# BMS_AFE_-_Cell_Balancing.net
KiCad netlist of a schematic drawn in Altium Designer
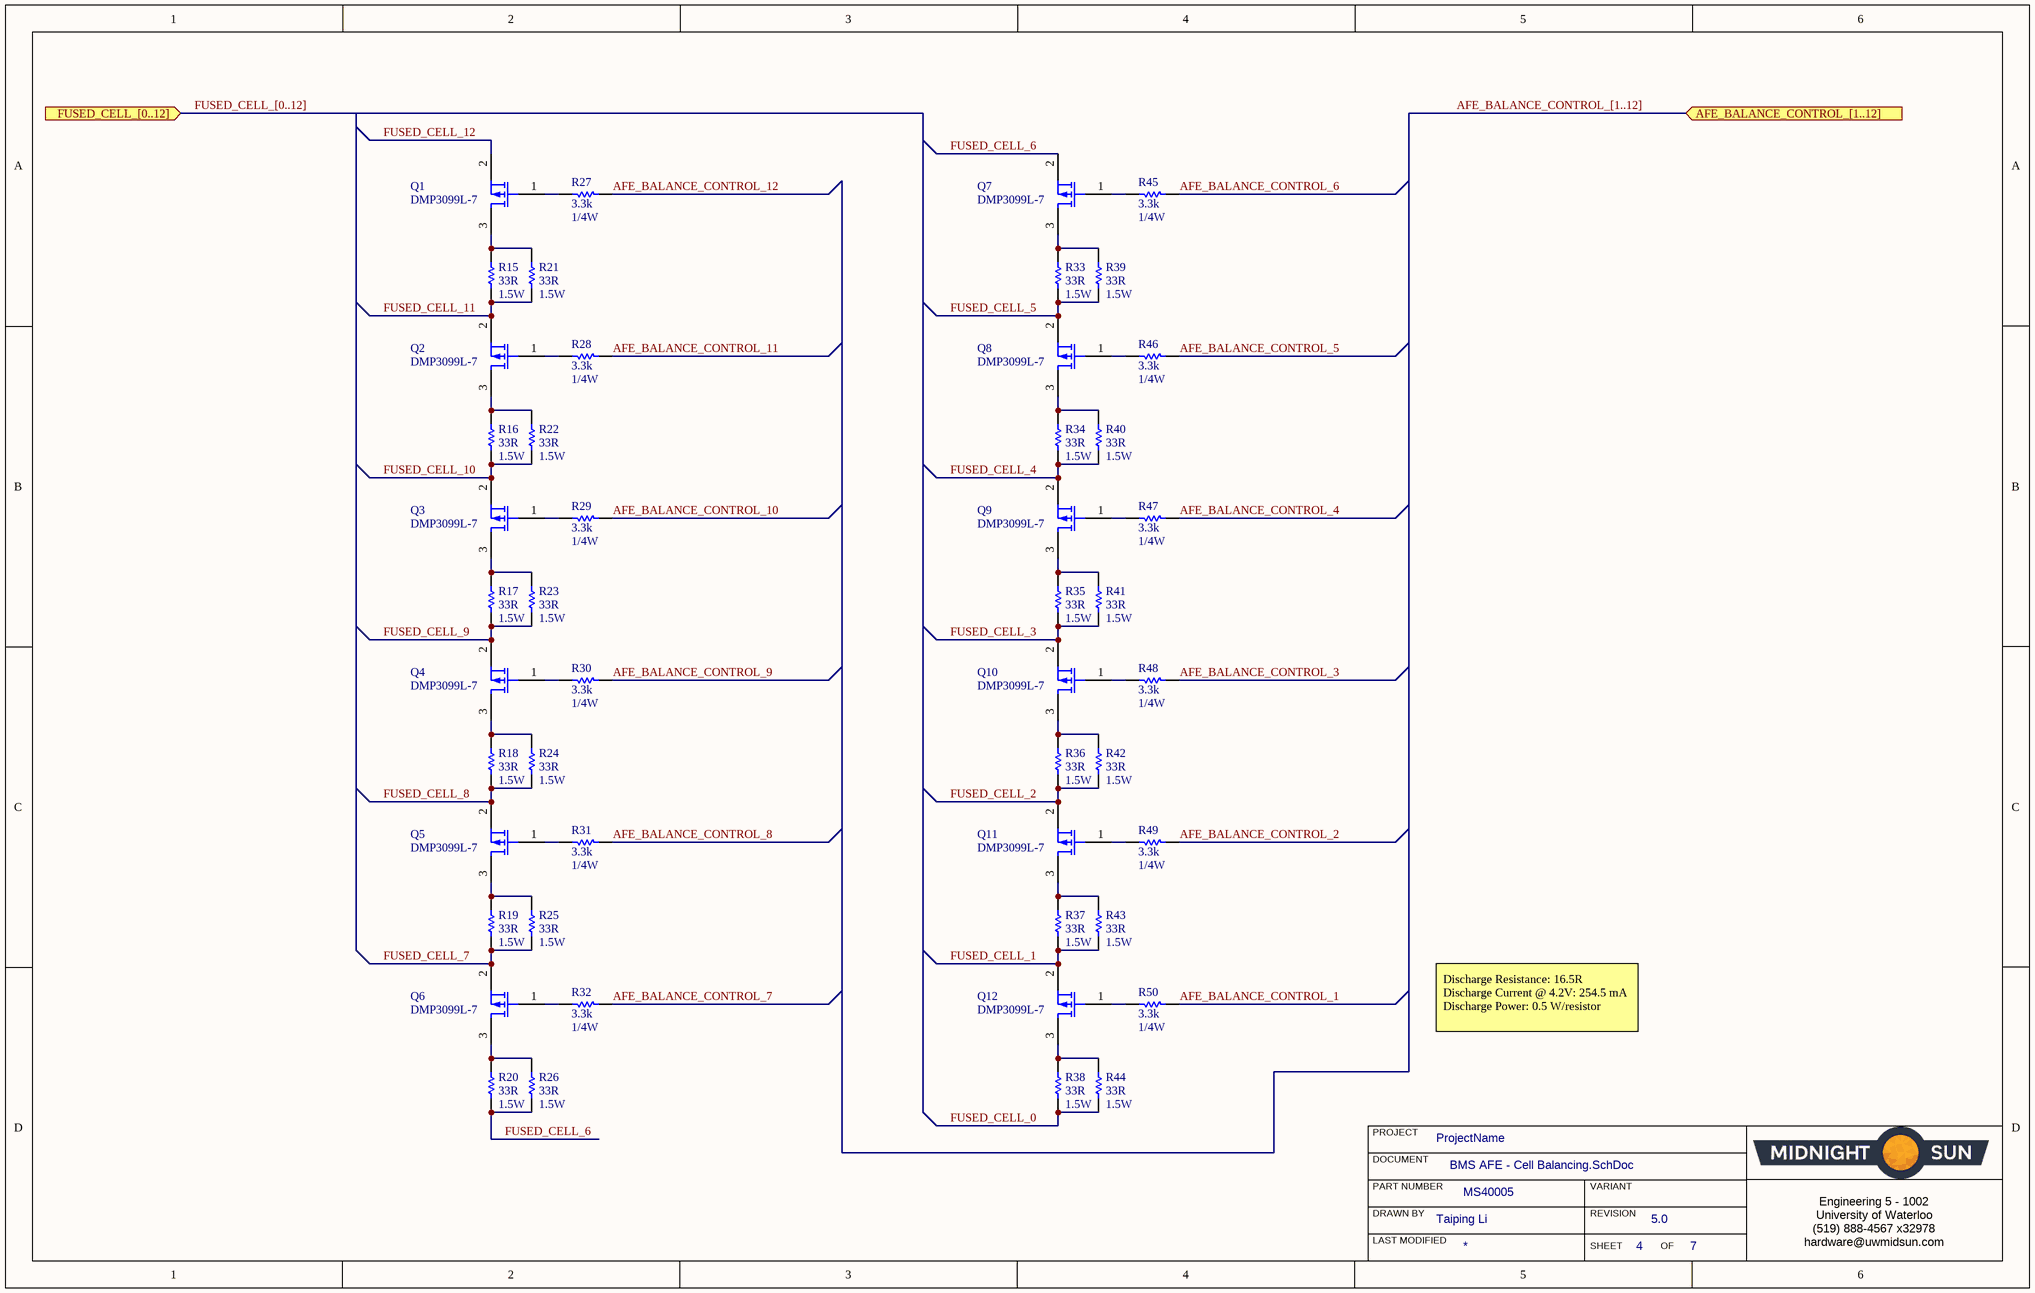
[diagram p0: BMS AFE - Cell Balancing.SchDoc]

(export (version "E")
  (design (tool "Eeschema 10.0.6"))
  (components
    (comp (ref "Q1")
      (value "MOSFET P-CH 30V 3.8A SOT-23")
      (footprint "MOSFET P-CH 30V 3.8A SOT-23")
      (description "P-Channel 30V 3.8A (Ta) 1.08W (Ta) Surface Mount SOT-23")
      (fields
        (field (name "MANUFACTURER") "Diodes Incorporated")
        (field (name "MANUFACTURER PART NUMBER") "DMP3099L-7")
      )
      (libsource (lib "Schematic Diagrams") (part "MOSFET P-CH 30V 3.8A SOT-23"))
    )
    (comp (ref "Q2")
      (value "MOSFET P-CH 30V 3.8A SOT-23")
      (footprint "MOSFET P-CH 30V 3.8A SOT-23")
      (description "P-Channel 30V 3.8A (Ta) 1.08W (Ta) Surface Mount SOT-23")
      (fields
        (field (name "MANUFACTURER") "Diodes Incorporated")
        (field (name "MANUFACTURER PART NUMBER") "DMP3099L-7")
      )
      (libsource (lib "Schematic Diagrams") (part "MOSFET P-CH 30V 3.8A SOT-23"))
    )
    (comp (ref "Q3")
      (value "MOSFET P-CH 30V 3.8A SOT-23")
      (footprint "MOSFET P-CH 30V 3.8A SOT-23")
      (description "P-Channel 30V 3.8A (Ta) 1.08W (Ta) Surface Mount SOT-23")
      (fields
        (field (name "MANUFACTURER") "Diodes Incorporated")
        (field (name "MANUFACTURER PART NUMBER") "DMP3099L-7")
      )
      (libsource (lib "Schematic Diagrams") (part "MOSFET P-CH 30V 3.8A SOT-23"))
    )
    (comp (ref "Q4")
      (value "MOSFET P-CH 30V 3.8A SOT-23")
      (footprint "MOSFET P-CH 30V 3.8A SOT-23")
      (description "P-Channel 30V 3.8A (Ta) 1.08W (Ta) Surface Mount SOT-23")
      (fields
        (field (name "MANUFACTURER") "Diodes Incorporated")
        (field (name "MANUFACTURER PART NUMBER") "DMP3099L-7")
      )
      (libsource (lib "Schematic Diagrams") (part "MOSFET P-CH 30V 3.8A SOT-23"))
    )
    (comp (ref "Q5")
      (value "MOSFET P-CH 30V 3.8A SOT-23")
      (footprint "MOSFET P-CH 30V 3.8A SOT-23")
      (description "P-Channel 30V 3.8A (Ta) 1.08W (Ta) Surface Mount SOT-23")
      (fields
        (field (name "MANUFACTURER") "Diodes Incorporated")
        (field (name "MANUFACTURER PART NUMBER") "DMP3099L-7")
      )
      (libsource (lib "Schematic Diagrams") (part "MOSFET P-CH 30V 3.8A SOT-23"))
    )
    (comp (ref "Q6")
      (value "MOSFET P-CH 30V 3.8A SOT-23")
      (footprint "MOSFET P-CH 30V 3.8A SOT-23")
      (description "P-Channel 30V 3.8A (Ta) 1.08W (Ta) Surface Mount SOT-23")
      (fields
        (field (name "MANUFACTURER") "Diodes Incorporated")
        (field (name "MANUFACTURER PART NUMBER") "DMP3099L-7")
      )
      (libsource (lib "Schematic Diagrams") (part "MOSFET P-CH 30V 3.8A SOT-23"))
    )
    (comp (ref "Q7")
      (value "MOSFET P-CH 30V 3.8A SOT-23")
      (footprint "MOSFET P-CH 30V 3.8A SOT-23")
      (description "P-Channel 30V 3.8A (Ta) 1.08W (Ta) Surface Mount SOT-23")
      (fields
        (field (name "MANUFACTURER") "Diodes Incorporated")
        (field (name "MANUFACTURER PART NUMBER") "DMP3099L-7")
      )
      (libsource (lib "Schematic Diagrams") (part "MOSFET P-CH 30V 3.8A SOT-23"))
    )
    (comp (ref "Q8")
      (value "MOSFET P-CH 30V 3.8A SOT-23")
      (footprint "MOSFET P-CH 30V 3.8A SOT-23")
      (description "P-Channel 30V 3.8A (Ta) 1.08W (Ta) Surface Mount SOT-23")
      (fields
        (field (name "MANUFACTURER") "Diodes Incorporated")
        (field (name "MANUFACTURER PART NUMBER") "DMP3099L-7")
      )
      (libsource (lib "Schematic Diagrams") (part "MOSFET P-CH 30V 3.8A SOT-23"))
    )
    (comp (ref "Q9")
      (value "MOSFET P-CH 30V 3.8A SOT-23")
      (footprint "MOSFET P-CH 30V 3.8A SOT-23")
      (description "P-Channel 30V 3.8A (Ta) 1.08W (Ta) Surface Mount SOT-23")
      (fields
        (field (name "MANUFACTURER") "Diodes Incorporated")
        (field (name "MANUFACTURER PART NUMBER") "DMP3099L-7")
      )
      (libsource (lib "Schematic Diagrams") (part "MOSFET P-CH 30V 3.8A SOT-23"))
    )
    (comp (ref "Q10")
      (value "MOSFET P-CH 30V 3.8A SOT-23")
      (footprint "MOSFET P-CH 30V 3.8A SOT-23")
      (description "P-Channel 30V 3.8A (Ta) 1.08W (Ta) Surface Mount SOT-23")
      (fields
        (field (name "MANUFACTURER") "Diodes Incorporated")
        (field (name "MANUFACTURER PART NUMBER") "DMP3099L-7")
      )
      (libsource (lib "Schematic Diagrams") (part "MOSFET P-CH 30V 3.8A SOT-23"))
    )
    (comp (ref "Q11")
      (value "MOSFET P-CH 30V 3.8A SOT-23")
      (footprint "MOSFET P-CH 30V 3.8A SOT-23")
      (description "P-Channel 30V 3.8A (Ta) 1.08W (Ta) Surface Mount SOT-23")
      (fields
        (field (name "MANUFACTURER") "Diodes Incorporated")
        (field (name "MANUFACTURER PART NUMBER") "DMP3099L-7")
      )
      (libsource (lib "Schematic Diagrams") (part "MOSFET P-CH 30V 3.8A SOT-23"))
    )
    (comp (ref "Q12")
      (value "MOSFET P-CH 30V 3.8A SOT-23")
      (footprint "MOSFET P-CH 30V 3.8A SOT-23")
      (description "P-Channel 30V 3.8A (Ta) 1.08W (Ta) Surface Mount SOT-23")
      (fields
        (field (name "MANUFACTURER") "Diodes Incorporated")
        (field (name "MANUFACTURER PART NUMBER") "DMP3099L-7")
      )
      (libsource (lib "Schematic Diagrams") (part "MOSFET P-CH 30V 3.8A SOT-23"))
    )
    (comp (ref "R15")
      (value "33R")
      (footprint "RES STACKPOLE RPC2512 2512")
      (fields
        (field (name "MANUFACTURER") "Stackpole Electronics Inc.")
        (field (name "MANUFACTURER PART NUMBER") "RPC2512JT33R0")
        (field (name "TOLERANCE") "±5%")
        (field (name "POWER (WATTS)") "1.5W")
      )
      (libsource (lib "Schematic Diagrams") (part "RES 33 OHM 5% 1.5W 2512"))
    )
    (comp (ref "R16")
      (value "33R")
      (footprint "RES STACKPOLE RPC2512 2512")
      (fields
        (field (name "MANUFACTURER") "Stackpole Electronics Inc.")
        (field (name "MANUFACTURER PART NUMBER") "RPC2512JT33R0")
        (field (name "TOLERANCE") "±5%")
        (field (name "POWER (WATTS)") "1.5W")
      )
      (libsource (lib "Schematic Diagrams") (part "RES 33 OHM 5% 1.5W 2512"))
    )
    (comp (ref "R17")
      (value "33R")
      (footprint "RES STACKPOLE RPC2512 2512")
      (fields
        (field (name "MANUFACTURER") "Stackpole Electronics Inc.")
        (field (name "MANUFACTURER PART NUMBER") "RPC2512JT33R0")
        (field (name "TOLERANCE") "±5%")
        (field (name "POWER (WATTS)") "1.5W")
      )
      (libsource (lib "Schematic Diagrams") (part "RES 33 OHM 5% 1.5W 2512"))
    )
    (comp (ref "R18")
      (value "33R")
      (footprint "RES STACKPOLE RPC2512 2512")
      (fields
        (field (name "MANUFACTURER") "Stackpole Electronics Inc.")
        (field (name "MANUFACTURER PART NUMBER") "RPC2512JT33R0")
        (field (name "TOLERANCE") "±5%")
        (field (name "POWER (WATTS)") "1.5W")
      )
      (libsource (lib "Schematic Diagrams") (part "RES 33 OHM 5% 1.5W 2512"))
    )
    (comp (ref "R19")
      (value "33R")
      (footprint "RES STACKPOLE RPC2512 2512")
      (fields
        (field (name "MANUFACTURER") "Stackpole Electronics Inc.")
        (field (name "MANUFACTURER PART NUMBER") "RPC2512JT33R0")
        (field (name "TOLERANCE") "±5%")
        (field (name "POWER (WATTS)") "1.5W")
      )
      (libsource (lib "Schematic Diagrams") (part "RES 33 OHM 5% 1.5W 2512"))
    )
    (comp (ref "R20")
      (value "33R")
      (footprint "RES STACKPOLE RPC2512 2512")
      (fields
        (field (name "MANUFACTURER") "Stackpole Electronics Inc.")
        (field (name "MANUFACTURER PART NUMBER") "RPC2512JT33R0")
        (field (name "TOLERANCE") "±5%")
        (field (name "POWER (WATTS)") "1.5W")
      )
      (libsource (lib "Schematic Diagrams") (part "RES 33 OHM 5% 1.5W 2512"))
    )
    (comp (ref "R21")
      (value "33R")
      (footprint "RES STACKPOLE RPC2512 2512")
      (fields
        (field (name "MANUFACTURER") "Stackpole Electronics Inc.")
        (field (name "MANUFACTURER PART NUMBER") "RPC2512JT33R0")
        (field (name "TOLERANCE") "±5%")
        (field (name "POWER (WATTS)") "1.5W")
      )
      (libsource (lib "Schematic Diagrams") (part "RES 33 OHM 5% 1.5W 2512"))
    )
    (comp (ref "R22")
      (value "33R")
      (footprint "RES STACKPOLE RPC2512 2512")
      (fields
        (field (name "MANUFACTURER") "Stackpole Electronics Inc.")
        (field (name "MANUFACTURER PART NUMBER") "RPC2512JT33R0")
        (field (name "TOLERANCE") "±5%")
        (field (name "POWER (WATTS)") "1.5W")
      )
      (libsource (lib "Schematic Diagrams") (part "RES 33 OHM 5% 1.5W 2512"))
    )
    (comp (ref "R23")
      (value "33R")
      (footprint "RES STACKPOLE RPC2512 2512")
      (fields
        (field (name "MANUFACTURER") "Stackpole Electronics Inc.")
        (field (name "MANUFACTURER PART NUMBER") "RPC2512JT33R0")
        (field (name "TOLERANCE") "±5%")
        (field (name "POWER (WATTS)") "1.5W")
      )
      (libsource (lib "Schematic Diagrams") (part "RES 33 OHM 5% 1.5W 2512"))
    )
    (comp (ref "R24")
      (value "33R")
      (footprint "RES STACKPOLE RPC2512 2512")
      (fields
        (field (name "MANUFACTURER") "Stackpole Electronics Inc.")
        (field (name "MANUFACTURER PART NUMBER") "RPC2512JT33R0")
        (field (name "TOLERANCE") "±5%")
        (field (name "POWER (WATTS)") "1.5W")
      )
      (libsource (lib "Schematic Diagrams") (part "RES 33 OHM 5% 1.5W 2512"))
    )
    (comp (ref "R25")
      (value "33R")
      (footprint "RES STACKPOLE RPC2512 2512")
      (fields
        (field (name "MANUFACTURER") "Stackpole Electronics Inc.")
        (field (name "MANUFACTURER PART NUMBER") "RPC2512JT33R0")
        (field (name "TOLERANCE") "±5%")
        (field (name "POWER (WATTS)") "1.5W")
      )
      (libsource (lib "Schematic Diagrams") (part "RES 33 OHM 5% 1.5W 2512"))
    )
    (comp (ref "R26")
      (value "33R")
      (footprint "RES STACKPOLE RPC2512 2512")
      (fields
        (field (name "MANUFACTURER") "Stackpole Electronics Inc.")
        (field (name "MANUFACTURER PART NUMBER") "RPC2512JT33R0")
        (field (name "TOLERANCE") "±5%")
        (field (name "POWER (WATTS)") "1.5W")
      )
      (libsource (lib "Schematic Diagrams") (part "RES 33 OHM 5% 1.5W 2512"))
    )
    (comp (ref "R27")
      (value "RES 3.3K OHM 1% 1/4W 0603")
      (footprint "RES, 0603")
      (fields
        (field (name "TOLERANCE") "±1%")
        (field (name "RESISTANCE") "3.3k")
        (field (name "POWER") "1/4W")
      )
      (libsource (lib "Schematic Diagrams") (part "RES 3.3K OHM 1% 1/4W 0603"))
    )
    (comp (ref "R28")
      (value "RES 3.3K OHM 1% 1/4W 0603")
      (footprint "RES, 0603")
      (fields
        (field (name "TOLERANCE") "±1%")
        (field (name "RESISTANCE") "3.3k")
        (field (name "POWER") "1/4W")
      )
      (libsource (lib "Schematic Diagrams") (part "RES 3.3K OHM 1% 1/4W 0603"))
    )
    (comp (ref "R29")
      (value "RES 3.3K OHM 1% 1/4W 0603")
      (footprint "RES, 0603")
      (fields
        (field (name "TOLERANCE") "±1%")
        (field (name "RESISTANCE") "3.3k")
        (field (name "POWER") "1/4W")
      )
      (libsource (lib "Schematic Diagrams") (part "RES 3.3K OHM 1% 1/4W 0603"))
    )
    (comp (ref "R30")
      (value "RES 3.3K OHM 1% 1/4W 0603")
      (footprint "RES, 0603")
      (fields
        (field (name "TOLERANCE") "±1%")
        (field (name "RESISTANCE") "3.3k")
        (field (name "POWER") "1/4W")
      )
      (libsource (lib "Schematic Diagrams") (part "RES 3.3K OHM 1% 1/4W 0603"))
    )
    (comp (ref "R31")
      (value "RES 3.3K OHM 1% 1/4W 0603")
      (footprint "RES, 0603")
      (fields
        (field (name "TOLERANCE") "±1%")
        (field (name "RESISTANCE") "3.3k")
        (field (name "POWER") "1/4W")
      )
      (libsource (lib "Schematic Diagrams") (part "RES 3.3K OHM 1% 1/4W 0603"))
    )
    (comp (ref "R32")
      (value "RES 3.3K OHM 1% 1/4W 0603")
      (footprint "RES, 0603")
      (fields
        (field (name "TOLERANCE") "±1%")
        (field (name "RESISTANCE") "3.3k")
        (field (name "POWER") "1/4W")
      )
      (libsource (lib "Schematic Diagrams") (part "RES 3.3K OHM 1% 1/4W 0603"))
    )
    (comp (ref "R33")
      (value "33R")
      (footprint "RES STACKPOLE RPC2512 2512")
      (fields
        (field (name "MANUFACTURER") "Stackpole Electronics Inc.")
        (field (name "MANUFACTURER PART NUMBER") "RPC2512JT33R0")
        (field (name "TOLERANCE") "±5%")
        (field (name "POWER (WATTS)") "1.5W")
      )
      (libsource (lib "Schematic Diagrams") (part "RES 33 OHM 5% 1.5W 2512"))
    )
    (comp (ref "R34")
      (value "33R")
      (footprint "RES STACKPOLE RPC2512 2512")
      (fields
        (field (name "MANUFACTURER") "Stackpole Electronics Inc.")
        (field (name "MANUFACTURER PART NUMBER") "RPC2512JT33R0")
        (field (name "TOLERANCE") "±5%")
        (field (name "POWER (WATTS)") "1.5W")
      )
      (libsource (lib "Schematic Diagrams") (part "RES 33 OHM 5% 1.5W 2512"))
    )
    (comp (ref "R35")
      (value "33R")
      (footprint "RES STACKPOLE RPC2512 2512")
      (fields
        (field (name "MANUFACTURER") "Stackpole Electronics Inc.")
        (field (name "MANUFACTURER PART NUMBER") "RPC2512JT33R0")
        (field (name "TOLERANCE") "±5%")
        (field (name "POWER (WATTS)") "1.5W")
      )
      (libsource (lib "Schematic Diagrams") (part "RES 33 OHM 5% 1.5W 2512"))
    )
    (comp (ref "R36")
      (value "33R")
      (footprint "RES STACKPOLE RPC2512 2512")
      (fields
        (field (name "MANUFACTURER") "Stackpole Electronics Inc.")
        (field (name "MANUFACTURER PART NUMBER") "RPC2512JT33R0")
        (field (name "TOLERANCE") "±5%")
        (field (name "POWER (WATTS)") "1.5W")
      )
      (libsource (lib "Schematic Diagrams") (part "RES 33 OHM 5% 1.5W 2512"))
    )
    (comp (ref "R37")
      (value "33R")
      (footprint "RES STACKPOLE RPC2512 2512")
      (fields
        (field (name "MANUFACTURER") "Stackpole Electronics Inc.")
        (field (name "MANUFACTURER PART NUMBER") "RPC2512JT33R0")
        (field (name "TOLERANCE") "±5%")
        (field (name "POWER (WATTS)") "1.5W")
      )
      (libsource (lib "Schematic Diagrams") (part "RES 33 OHM 5% 1.5W 2512"))
    )
    (comp (ref "R38")
      (value "33R")
      (footprint "RES STACKPOLE RPC2512 2512")
      (fields
        (field (name "MANUFACTURER") "Stackpole Electronics Inc.")
        (field (name "MANUFACTURER PART NUMBER") "RPC2512JT33R0")
        (field (name "TOLERANCE") "±5%")
        (field (name "POWER (WATTS)") "1.5W")
      )
      (libsource (lib "Schematic Diagrams") (part "RES 33 OHM 5% 1.5W 2512"))
    )
    (comp (ref "R39")
      (value "33R")
      (footprint "RES STACKPOLE RPC2512 2512")
      (fields
        (field (name "MANUFACTURER") "Stackpole Electronics Inc.")
        (field (name "MANUFACTURER PART NUMBER") "RPC2512JT33R0")
        (field (name "TOLERANCE") "±5%")
        (field (name "POWER (WATTS)") "1.5W")
      )
      (libsource (lib "Schematic Diagrams") (part "RES 33 OHM 5% 1.5W 2512"))
    )
    (comp (ref "R40")
      (value "33R")
      (footprint "RES STACKPOLE RPC2512 2512")
      (fields
        (field (name "MANUFACTURER") "Stackpole Electronics Inc.")
        (field (name "MANUFACTURER PART NUMBER") "RPC2512JT33R0")
        (field (name "TOLERANCE") "±5%")
        (field (name "POWER (WATTS)") "1.5W")
      )
      (libsource (lib "Schematic Diagrams") (part "RES 33 OHM 5% 1.5W 2512"))
    )
    (comp (ref "R41")
      (value "33R")
      (footprint "RES STACKPOLE RPC2512 2512")
      (fields
        (field (name "MANUFACTURER") "Stackpole Electronics Inc.")
        (field (name "MANUFACTURER PART NUMBER") "RPC2512JT33R0")
        (field (name "TOLERANCE") "±5%")
        (field (name "POWER (WATTS)") "1.5W")
      )
      (libsource (lib "Schematic Diagrams") (part "RES 33 OHM 5% 1.5W 2512"))
    )
    (comp (ref "R42")
      (value "33R")
      (footprint "RES STACKPOLE RPC2512 2512")
      (fields
        (field (name "MANUFACTURER") "Stackpole Electronics Inc.")
        (field (name "MANUFACTURER PART NUMBER") "RPC2512JT33R0")
        (field (name "TOLERANCE") "±5%")
        (field (name "POWER (WATTS)") "1.5W")
      )
      (libsource (lib "Schematic Diagrams") (part "RES 33 OHM 5% 1.5W 2512"))
    )
    (comp (ref "R43")
      (value "33R")
      (footprint "RES STACKPOLE RPC2512 2512")
      (fields
        (field (name "MANUFACTURER") "Stackpole Electronics Inc.")
        (field (name "MANUFACTURER PART NUMBER") "RPC2512JT33R0")
        (field (name "TOLERANCE") "±5%")
        (field (name "POWER (WATTS)") "1.5W")
      )
      (libsource (lib "Schematic Diagrams") (part "RES 33 OHM 5% 1.5W 2512"))
    )
    (comp (ref "R44")
      (value "33R")
      (footprint "RES STACKPOLE RPC2512 2512")
      (fields
        (field (name "MANUFACTURER") "Stackpole Electronics Inc.")
        (field (name "MANUFACTURER PART NUMBER") "RPC2512JT33R0")
        (field (name "TOLERANCE") "±5%")
        (field (name "POWER (WATTS)") "1.5W")
      )
      (libsource (lib "Schematic Diagrams") (part "RES 33 OHM 5% 1.5W 2512"))
    )
    (comp (ref "R45")
      (value "RES 3.3K OHM 1% 1/4W 0603")
      (footprint "RES, 0603")
      (fields
        (field (name "TOLERANCE") "±1%")
        (field (name "RESISTANCE") "3.3k")
        (field (name "POWER") "1/4W")
      )
      (libsource (lib "Schematic Diagrams") (part "RES 3.3K OHM 1% 1/4W 0603"))
    )
    (comp (ref "R46")
      (value "RES 3.3K OHM 1% 1/4W 0603")
      (footprint "RES, 0603")
      (fields
        (field (name "TOLERANCE") "±1%")
        (field (name "RESISTANCE") "3.3k")
        (field (name "POWER") "1/4W")
      )
      (libsource (lib "Schematic Diagrams") (part "RES 3.3K OHM 1% 1/4W 0603"))
    )
    (comp (ref "R47")
      (value "RES 3.3K OHM 1% 1/4W 0603")
      (footprint "RES, 0603")
      (fields
        (field (name "TOLERANCE") "±1%")
        (field (name "RESISTANCE") "3.3k")
        (field (name "POWER") "1/4W")
      )
      (libsource (lib "Schematic Diagrams") (part "RES 3.3K OHM 1% 1/4W 0603"))
    )
    (comp (ref "R48")
      (value "RES 3.3K OHM 1% 1/4W 0603")
      (footprint "RES, 0603")
      (fields
        (field (name "TOLERANCE") "±1%")
        (field (name "RESISTANCE") "3.3k")
        (field (name "POWER") "1/4W")
      )
      (libsource (lib "Schematic Diagrams") (part "RES 3.3K OHM 1% 1/4W 0603"))
    )
    (comp (ref "R49")
      (value "RES 3.3K OHM 1% 1/4W 0603")
      (footprint "RES, 0603")
      (fields
        (field (name "TOLERANCE") "±1%")
        (field (name "RESISTANCE") "3.3k")
        (field (name "POWER") "1/4W")
      )
      (libsource (lib "Schematic Diagrams") (part "RES 3.3K OHM 1% 1/4W 0603"))
    )
    (comp (ref "R50")
      (value "RES 3.3K OHM 1% 1/4W 0603")
      (footprint "RES, 0603")
      (fields
        (field (name "TOLERANCE") "±1%")
        (field (name "RESISTANCE") "3.3k")
        (field (name "POWER") "1/4W")
      )
      (libsource (lib "Schematic Diagrams") (part "RES 3.3K OHM 1% 1/4W 0603"))
    )
  )
  (nets
    (net (code "1") (name "/AFE_BALANCE_CONTROL_1") (class "Default")
      (node (ref "R50") (pin "1") (pinfunction "1_1") (pintype "passive"))
    )
    (net (code "2") (name "/AFE_BALANCE_CONTROL_2") (class "Default")
      (node (ref "R49") (pin "1") (pinfunction "1_1") (pintype "passive"))
    )
    (net (code "3") (name "/AFE_BALANCE_CONTROL_3") (class "Default")
      (node (ref "R48") (pin "1") (pinfunction "1_1") (pintype "passive"))
    )
    (net (code "4") (name "/AFE_BALANCE_CONTROL_4") (class "Default")
      (node (ref "R47") (pin "1") (pinfunction "1_1") (pintype "passive"))
    )
    (net (code "5") (name "/AFE_BALANCE_CONTROL_5") (class "Default")
      (node (ref "R46") (pin "1") (pinfunction "1_1") (pintype "passive"))
    )
    (net (code "6") (name "/AFE_BALANCE_CONTROL_6") (class "Default")
      (node (ref "R45") (pin "1") (pinfunction "1_1") (pintype "passive"))
    )
    (net (code "7") (name "/AFE_BALANCE_CONTROL_7") (class "Default")
      (node (ref "R32") (pin "1") (pinfunction "1_1") (pintype "passive"))
    )
    (net (code "8") (name "/AFE_BALANCE_CONTROL_8") (class "Default")
      (node (ref "R31") (pin "1") (pinfunction "1_1") (pintype "passive"))
    )
    (net (code "9") (name "/AFE_BALANCE_CONTROL_9") (class "Default")
      (node (ref "R30") (pin "1") (pinfunction "1_1") (pintype "passive"))
    )
    (net (code "10") (name "/AFE_BALANCE_CONTROL_10") (class "Default")
      (node (ref "R29") (pin "1") (pinfunction "1_1") (pintype "passive"))
    )
    (net (code "11") (name "/AFE_BALANCE_CONTROL_11") (class "Default")
      (node (ref "R28") (pin "1") (pinfunction "1_1") (pintype "passive"))
    )
    (net (code "12") (name "/AFE_BALANCE_CONTROL_12") (class "Default")
      (node (ref "R27") (pin "1") (pinfunction "1_1") (pintype "passive"))
    )
    (net (code "14") (name "/FUSED_CELL_0") (class "Default")
      (node (ref "R38") (pin "2") (pinfunction "2_2") (pintype "passive"))
      (node (ref "R44") (pin "2") (pinfunction "2_2") (pintype "passive"))
    )
    (net (code "15") (name "/FUSED_CELL_1") (class "Default")
      (node (ref "Q12") (pin "2") (pinfunction "S_2") (pintype "passive"))
      (node (ref "R37") (pin "2") (pinfunction "2_2") (pintype "passive"))
      (node (ref "R43") (pin "2") (pinfunction "2_2") (pintype "passive"))
    )
    (net (code "16") (name "/FUSED_CELL_2") (class "Default")
      (node (ref "Q11") (pin "2") (pinfunction "S_2") (pintype "passive"))
      (node (ref "R36") (pin "2") (pinfunction "2_2") (pintype "passive"))
      (node (ref "R42") (pin "2") (pinfunction "2_2") (pintype "passive"))
    )
    (net (code "17") (name "/FUSED_CELL_3") (class "Default")
      (node (ref "Q10") (pin "2") (pinfunction "S_2") (pintype "passive"))
      (node (ref "R35") (pin "2") (pinfunction "2_2") (pintype "passive"))
      (node (ref "R41") (pin "2") (pinfunction "2_2") (pintype "passive"))
    )
    (net (code "18") (name "/FUSED_CELL_4") (class "Default")
      (node (ref "Q9") (pin "2") (pinfunction "S_2") (pintype "passive"))
      (node (ref "R34") (pin "2") (pinfunction "2_2") (pintype "passive"))
      (node (ref "R40") (pin "2") (pinfunction "2_2") (pintype "passive"))
    )
    (net (code "19") (name "/FUSED_CELL_5") (class "Default")
      (node (ref "Q8") (pin "2") (pinfunction "S_2") (pintype "passive"))
      (node (ref "R33") (pin "2") (pinfunction "2_2") (pintype "passive"))
      (node (ref "R39") (pin "2") (pinfunction "2_2") (pintype "passive"))
    )
    (net (code "20") (name "/FUSED_CELL_6") (class "Default")
      (node (ref "Q7") (pin "2") (pinfunction "S_2") (pintype "passive"))
      (node (ref "R20") (pin "2") (pinfunction "2_2") (pintype "passive"))
      (node (ref "R26") (pin "2") (pinfunction "2_2") (pintype "passive"))
    )
    (net (code "21") (name "/FUSED_CELL_7") (class "Default")
      (node (ref "Q6") (pin "2") (pinfunction "S_2") (pintype "passive"))
      (node (ref "R19") (pin "2") (pinfunction "2_2") (pintype "passive"))
      (node (ref "R25") (pin "2") (pinfunction "2_2") (pintype "passive"))
    )
    (net (code "22") (name "/FUSED_CELL_8") (class "Default")
      (node (ref "Q5") (pin "2") (pinfunction "S_2") (pintype "passive"))
      (node (ref "R18") (pin "2") (pinfunction "2_2") (pintype "passive"))
      (node (ref "R24") (pin "2") (pinfunction "2_2") (pintype "passive"))
    )
    (net (code "23") (name "/FUSED_CELL_9") (class "Default")
      (node (ref "Q4") (pin "2") (pinfunction "S_2") (pintype "passive"))
      (node (ref "R17") (pin "2") (pinfunction "2_2") (pintype "passive"))
      (node (ref "R23") (pin "2") (pinfunction "2_2") (pintype "passive"))
    )
    (net (code "24") (name "/FUSED_CELL_10") (class "Default")
      (node (ref "Q3") (pin "2") (pinfunction "S_2") (pintype "passive"))
      (node (ref "R16") (pin "2") (pinfunction "2_2") (pintype "passive"))
      (node (ref "R22") (pin "2") (pinfunction "2_2") (pintype "passive"))
    )
    (net (code "25") (name "/FUSED_CELL_11") (class "Default")
      (node (ref "Q2") (pin "2") (pinfunction "S_2") (pintype "passive"))
      (node (ref "R15") (pin "2") (pinfunction "2_2") (pintype "passive"))
      (node (ref "R21") (pin "2") (pinfunction "2_2") (pintype "passive"))
    )
    (net (code "26") (name "/FUSED_CELL_12") (class "Default")
      (node (ref "Q1") (pin "2") (pinfunction "S_2") (pintype "passive"))
    )
    (net (code "28") (name "Net-(Q1-D)") (class "Default")
      (node (ref "Q1") (pin "3") (pinfunction "D_3") (pintype "passive"))
      (node (ref "R15") (pin "1") (pinfunction "1_1") (pintype "passive"))
      (node (ref "R21") (pin "1") (pinfunction "1_1") (pintype "passive"))
    )
    (net (code "29") (name "Net-(Q1-G)") (class "Default")
      (node (ref "Q1") (pin "1") (pinfunction "G_1") (pintype "passive"))
      (node (ref "R27") (pin "2") (pinfunction "2_2") (pintype "passive"))
    )
    (net (code "30") (name "Net-(Q2-D)") (class "Default")
      (node (ref "Q2") (pin "3") (pinfunction "D_3") (pintype "passive"))
      (node (ref "R16") (pin "1") (pinfunction "1_1") (pintype "passive"))
      (node (ref "R22") (pin "1") (pinfunction "1_1") (pintype "passive"))
    )
    (net (code "31") (name "Net-(Q2-G)") (class "Default")
      (node (ref "Q2") (pin "1") (pinfunction "G_1") (pintype "passive"))
      (node (ref "R28") (pin "2") (pinfunction "2_2") (pintype "passive"))
    )
    (net (code "32") (name "Net-(Q3-D)") (class "Default")
      (node (ref "Q3") (pin "3") (pinfunction "D_3") (pintype "passive"))
      (node (ref "R17") (pin "1") (pinfunction "1_1") (pintype "passive"))
      (node (ref "R23") (pin "1") (pinfunction "1_1") (pintype "passive"))
    )
    (net (code "33") (name "Net-(Q3-G)") (class "Default")
      (node (ref "Q3") (pin "1") (pinfunction "G_1") (pintype "passive"))
      (node (ref "R29") (pin "2") (pinfunction "2_2") (pintype "passive"))
    )
    (net (code "34") (name "Net-(Q4-D)") (class "Default")
      (node (ref "Q4") (pin "3") (pinfunction "D_3") (pintype "passive"))
      (node (ref "R18") (pin "1") (pinfunction "1_1") (pintype "passive"))
      (node (ref "R24") (pin "1") (pinfunction "1_1") (pintype "passive"))
    )
    (net (code "35") (name "Net-(Q4-G)") (class "Default")
      (node (ref "Q4") (pin "1") (pinfunction "G_1") (pintype "passive"))
      (node (ref "R30") (pin "2") (pinfunction "2_2") (pintype "passive"))
    )
    (net (code "36") (name "Net-(Q5-D)") (class "Default")
      (node (ref "Q5") (pin "3") (pinfunction "D_3") (pintype "passive"))
      (node (ref "R19") (pin "1") (pinfunction "1_1") (pintype "passive"))
      (node (ref "R25") (pin "1") (pinfunction "1_1") (pintype "passive"))
    )
    (net (code "37") (name "Net-(Q5-G)") (class "Default")
      (node (ref "Q5") (pin "1") (pinfunction "G_1") (pintype "passive"))
      (node (ref "R31") (pin "2") (pinfunction "2_2") (pintype "passive"))
    )
    (net (code "38") (name "Net-(Q6-D)") (class "Default")
      (node (ref "Q6") (pin "3") (pinfunction "D_3") (pintype "passive"))
      (node (ref "R20") (pin "1") (pinfunction "1_1") (pintype "passive"))
      (node (ref "R26") (pin "1") (pinfunction "1_1") (pintype "passive"))
    )
    (net (code "39") (name "Net-(Q6-G)") (class "Default")
      (node (ref "Q6") (pin "1") (pinfunction "G_1") (pintype "passive"))
      (node (ref "R32") (pin "2") (pinfunction "2_2") (pintype "passive"))
    )
    (net (code "40") (name "Net-(Q7-D)") (class "Default")
      (node (ref "Q7") (pin "3") (pinfunction "D_3") (pintype "passive"))
      (node (ref "R33") (pin "1") (pinfunction "1_1") (pintype "passive"))
      (node (ref "R39") (pin "1") (pinfunction "1_1") (pintype "passive"))
    )
    (net (code "41") (name "Net-(Q7-G)") (class "Default")
      (node (ref "Q7") (pin "1") (pinfunction "G_1") (pintype "passive"))
      (node (ref "R45") (pin "2") (pinfunction "2_2") (pintype "passive"))
    )
    (net (code "42") (name "Net-(Q8-D)") (class "Default")
      (node (ref "Q8") (pin "3") (pinfunction "D_3") (pintype "passive"))
      (node (ref "R34") (pin "1") (pinfunction "1_1") (pintype "passive"))
      (node (ref "R40") (pin "1") (pinfunction "1_1") (pintype "passive"))
    )
    (net (code "43") (name "Net-(Q8-G)") (class "Default")
      (node (ref "Q8") (pin "1") (pinfunction "G_1") (pintype "passive"))
      (node (ref "R46") (pin "2") (pinfunction "2_2") (pintype "passive"))
    )
    (net (code "44") (name "Net-(Q9-D)") (class "Default")
      (node (ref "Q9") (pin "3") (pinfunction "D_3") (pintype "passive"))
      (node (ref "R35") (pin "1") (pinfunction "1_1") (pintype "passive"))
      (node (ref "R41") (pin "1") (pinfunction "1_1") (pintype "passive"))
    )
    (net (code "45") (name "Net-(Q9-G)") (class "Default")
      (node (ref "Q9") (pin "1") (pinfunction "G_1") (pintype "passive"))
      (node (ref "R47") (pin "2") (pinfunction "2_2") (pintype "passive"))
    )
    (net (code "46") (name "Net-(Q10-D)") (class "Default")
      (node (ref "Q10") (pin "3") (pinfunction "D_3") (pintype "passive"))
      (node (ref "R36") (pin "1") (pinfunction "1_1") (pintype "passive"))
      (node (ref "R42") (pin "1") (pinfunction "1_1") (pintype "passive"))
    )
    (net (code "47") (name "Net-(Q10-G)") (class "Default")
      (node (ref "Q10") (pin "1") (pinfunction "G_1") (pintype "passive"))
      (node (ref "R48") (pin "2") (pinfunction "2_2") (pintype "passive"))
    )
    (net (code "48") (name "Net-(Q11-D)") (class "Default")
      (node (ref "Q11") (pin "3") (pinfunction "D_3") (pintype "passive"))
      (node (ref "R37") (pin "1") (pinfunction "1_1") (pintype "passive"))
      (node (ref "R43") (pin "1") (pinfunction "1_1") (pintype "passive"))
    )
    (net (code "49") (name "Net-(Q11-G)") (class "Default")
      (node (ref "Q11") (pin "1") (pinfunction "G_1") (pintype "passive"))
      (node (ref "R49") (pin "2") (pinfunction "2_2") (pintype "passive"))
    )
    (net (code "50") (name "Net-(Q12-D)") (class "Default")
      (node (ref "Q12") (pin "3") (pinfunction "D_3") (pintype "passive"))
      (node (ref "R38") (pin "1") (pinfunction "1_1") (pintype "passive"))
      (node (ref "R44") (pin "1") (pinfunction "1_1") (pintype "passive"))
    )
    (net (code "51") (name "Net-(Q12-G)") (class "Default")
      (node (ref "Q12") (pin "1") (pinfunction "G_1") (pintype "passive"))
      (node (ref "R50") (pin "2") (pinfunction "2_2") (pintype "passive"))
    )
  )
)
